# 07-LVDS.net
KiCad netlist of a schematic drawn in Altium Designer
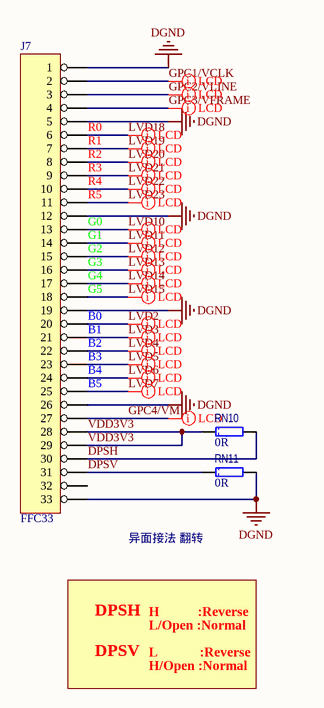
[diagram p0: 07-LVDS.SchDoc]

(export (version "E")
  (design (tool "Eeschema 10.0.6"))
  (components
    (comp (ref "J7")
      (value "FFC33")
      (footprint "FFC/SM0.5-2H33")
      (description "CON")
      (libsource (lib "*") (part "HEADER 33"))
    )
    (comp (ref "RN10")
      (value "0R")
      (footprint "1608[0603]RN")
      (description "厚膜电阻器 - SMD 1/10watt ZEROohm Jumper")
      (fields
        (field (name "MANUFACTURER") "Vishay / Dale")
        (field (name "MANUFACTURER PART NUMBER") "CRCW06030000ZSTA")
      )
      (libsource (lib "0R 1%") (part "RES"))
    )
    (comp (ref "RN11")
      (value "0R")
      (footprint "1608[0603]RN")
      (description "厚膜电阻器 - SMD 1/10watt ZEROohm Jumper")
      (fields
        (field (name "MANUFACTURER") "Vishay / Dale")
        (field (name "MANUFACTURER PART NUMBER") "CRCW06030000ZSTA")
      )
      (libsource (lib "0R 1%") (part "RES"))
    )
  )
  (nets
    (net (code "2") (name "/DPSH") (class "Default")
      (node (ref "J7") (pin "30") (pinfunction "30_30") (pintype "passive"))
      (node (ref "RN10") (pin "2") (pinfunction "2_2") (pintype "passive"))
    )
    (net (code "3") (name "/DPSV") (class "Default")
      (node (ref "J7") (pin "31") (pinfunction "31_31") (pintype "passive"))
      (node (ref "RN11") (pin "1") (pinfunction "1_1") (pintype "passive"))
    )
    (net (code "4") (name "/GPC1{slash}VCLK") (class "Default")
      (node (ref "J7") (pin "2") (pinfunction "2_2") (pintype "passive"))
    )
    (net (code "5") (name "/GPC2{slash}VLINE") (class "Default")
      (node (ref "J7") (pin "3") (pinfunction "3_3") (pintype "passive"))
    )
    (net (code "6") (name "/GPC3{slash}VFRAME") (class "Default")
      (node (ref "J7") (pin "4") (pinfunction "4_4") (pintype "passive"))
    )
    (net (code "7") (name "/GPC4{slash}VM") (class "Default")
      (node (ref "J7") (pin "27") (pinfunction "27_27") (pintype "passive"))
    )
    (net (code "8") (name "/LVD2") (class "Default")
      (node (ref "J7") (pin "20") (pinfunction "20_20") (pintype "passive"))
    )
    (net (code "9") (name "/LVD3") (class "Default")
      (node (ref "J7") (pin "21") (pinfunction "21_21") (pintype "passive"))
    )
    (net (code "10") (name "/LVD4") (class "Default")
      (node (ref "J7") (pin "22") (pinfunction "22_22") (pintype "passive"))
    )
    (net (code "11") (name "/LVD5") (class "Default")
      (node (ref "J7") (pin "23") (pinfunction "23_23") (pintype "passive"))
    )
    (net (code "12") (name "/LVD6") (class "Default")
      (node (ref "J7") (pin "24") (pinfunction "24_24") (pintype "passive"))
    )
    (net (code "13") (name "/LVD7") (class "Default")
      (node (ref "J7") (pin "25") (pinfunction "25_25") (pintype "passive"))
    )
    (net (code "14") (name "/LVD10") (class "Default")
      (node (ref "J7") (pin "13") (pinfunction "13_13") (pintype "passive"))
    )
    (net (code "15") (name "/LVD11") (class "Default")
      (node (ref "J7") (pin "14") (pinfunction "14_14") (pintype "passive"))
    )
    (net (code "16") (name "/LVD12") (class "Default")
      (node (ref "J7") (pin "15") (pinfunction "15_15") (pintype "passive"))
    )
    (net (code "17") (name "/LVD13") (class "Default")
      (node (ref "J7") (pin "16") (pinfunction "16_16") (pintype "passive"))
    )
    (net (code "18") (name "/LVD14") (class "Default")
      (node (ref "J7") (pin "17") (pinfunction "17_17") (pintype "passive"))
    )
    (net (code "19") (name "/LVD15") (class "Default")
      (node (ref "J7") (pin "18") (pinfunction "18_18") (pintype "passive"))
    )
    (net (code "20") (name "/LVD18") (class "Default")
      (node (ref "J7") (pin "6") (pinfunction "6_6") (pintype "passive"))
    )
    (net (code "21") (name "/LVD19") (class "Default")
      (node (ref "J7") (pin "7") (pinfunction "7_7") (pintype "passive"))
    )
    (net (code "22") (name "/LVD20") (class "Default")
      (node (ref "J7") (pin "8") (pinfunction "8_8") (pintype "passive"))
    )
    (net (code "23") (name "/LVD21") (class "Default")
      (node (ref "J7") (pin "9") (pinfunction "9_9") (pintype "passive"))
    )
    (net (code "24") (name "/LVD22") (class "Default")
      (node (ref "J7") (pin "10") (pinfunction "10_10") (pintype "passive"))
    )
    (net (code "25") (name "/LVD23") (class "Default")
      (node (ref "J7") (pin "11") (pinfunction "11_11") (pintype "passive"))
    )
    (net (code "26") (name "/VDD3V3") (class "Default")
      (node (ref "J7") (pin "28") (pinfunction "28_28") (pintype "passive"))
      (node (ref "J7") (pin "29") (pinfunction "29_29") (pintype "passive"))
      (node (ref "RN10") (pin "1") (pinfunction "1_1") (pintype "passive"))
    )
    (net (code "27") (name "DGND") (class "Default")
      (node (ref "J7") (pin "1") (pinfunction "1_1") (pintype "passive"))
      (node (ref "J7") (pin "12") (pinfunction "12_12") (pintype "passive"))
      (node (ref "J7") (pin "19") (pinfunction "19_19") (pintype "passive"))
      (node (ref "J7") (pin "26") (pinfunction "26_26") (pintype "passive"))
      (node (ref "J7") (pin "33") (pinfunction "33_33") (pintype "passive"))
      (node (ref "J7") (pin "5") (pinfunction "5_5") (pintype "passive"))
      (node (ref "RN11") (pin "2") (pinfunction "2_2") (pintype "passive"))
    )
    (net (code "28") (name "unconnected-(J7-Pad32)") (class "Default")
      (node (ref "J7") (pin "32") (pinfunction "32_32") (pintype "passive"))
    )
  )
)
